# DC_SUPPLY.net
KiCad netlist of a schematic drawn in Altium Designer
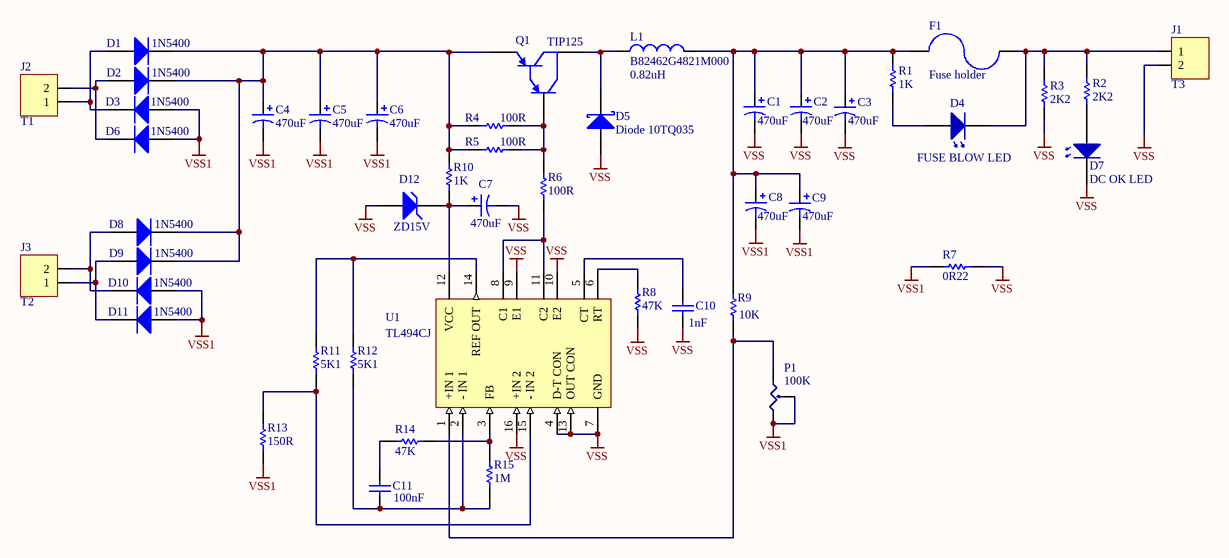
[diagram p0: DC SUPPLY.SchDoc]

(export (version "E")
  (design (tool "Eeschema 10.0.6"))
  (components
    (comp (ref "C1")
      (value "470uF")
      (footprint "CAPPR5-10X16")
      (description "Aluminum Electrolytic Capacitor, Radial Style with Long Leads: 470uF, 35V")
      (fields (field (name "PUBLISHER") "Altium Limited"))
      (libsource (lib "Vishay Roederstein Electrolytic Radial-Lead Capacitor") (part "EKA00DD347F00"))
    )
    (comp (ref "C2")
      (value "470uF")
      (footprint "CAPPR5-10X16")
      (description "Aluminum Electrolytic Capacitor, Radial Style with Long Leads: 470uF, 35V")
      (fields (field (name "PUBLISHER") "Altium Limited"))
      (libsource (lib "Vishay Roederstein Electrolytic Radial-Lead Capacitor") (part "EKA00DD347F00"))
    )
    (comp (ref "C3")
      (value "470uF")
      (footprint "CAPPR5-10X16")
      (description "Aluminum Electrolytic Capacitor, Radial Style with Long Leads: 470uF, 35V")
      (fields (field (name "PUBLISHER") "Altium Limited"))
      (libsource (lib "Vishay Roederstein Electrolytic Radial-Lead Capacitor") (part "EKA00DD347F00"))
    )
    (comp (ref "C4")
      (value "470uF")
      (footprint "CAPPR5-10X16")
      (description "Aluminum Electrolytic Capacitor, Radial Style with Long Leads: 470uF, 35V")
      (fields (field (name "PUBLISHER") "Altium Limited"))
      (libsource (lib "Vishay Roederstein Electrolytic Radial-Lead Capacitor") (part "EKA00DD347F00"))
    )
    (comp (ref "C5")
      (value "470uF")
      (footprint "CAPPR5-10X16")
      (description "Aluminum Electrolytic Capacitor, Radial Style with Long Leads: 470uF, 35V")
      (fields (field (name "PUBLISHER") "Altium Limited"))
      (libsource (lib "Vishay Roederstein Electrolytic Radial-Lead Capacitor") (part "EKA00DD347F00"))
    )
    (comp (ref "C6")
      (value "470uF")
      (footprint "CAPPR5-10X16")
      (description "Aluminum Electrolytic Capacitor, Radial Style with Long Leads: 470uF, 35V")
      (fields (field (name "PUBLISHER") "Altium Limited"))
      (libsource (lib "Vishay Roederstein Electrolytic Radial-Lead Capacitor") (part "EKA00DD347F00"))
    )
    (comp (ref "C7")
      (value "470uF")
      (footprint "CAPPR5-10X16")
      (description "Aluminum Electrolytic Capacitor, Radial Style with Long Leads: 470uF, 35V")
      (fields (field (name "PUBLISHER") "Altium Limited"))
      (libsource (lib "Vishay Roederstein Electrolytic Radial-Lead Capacitor") (part "EKA00DD347F00"))
    )
    (comp (ref "C8")
      (value "470uF")
      (footprint "CAPPR5-10X16")
      (description "Aluminum Electrolytic Capacitor, Radial Style with Long Leads: 470uF, 35V")
      (fields (field (name "PUBLISHER") "Altium Limited"))
      (libsource (lib "Vishay Roederstein Electrolytic Radial-Lead Capacitor") (part "EKA00DD347F00"))
    )
    (comp (ref "C9")
      (value "470uF")
      (footprint "CAPPR5-10X16")
      (description "Aluminum Electrolytic Capacitor, Radial Style with Long Leads: 470uF, 35V")
      (fields (field (name "PUBLISHER") "Altium Limited"))
      (libsource (lib "Vishay Roederstein Electrolytic Radial-Lead Capacitor") (part "EKA00DD347F00"))
    )
    (comp (ref "C10")
      (value "1nF")
      (footprint "0805")
      (description "Ceramic Chip Capacitor - Standard")
      (fields (field (name "PUBLISHER") "Altium Limited"))
      (libsource (lib "KEMET Chip Capacitor") (part "C0805"))
    )
    (comp (ref "C11")
      (value "100nF")
      (footprint "0805")
      (description "Ceramic Chip Capacitor - Standard")
      (fields (field (name "PUBLISHER") "Altium Limited"))
      (libsource (lib "KEMET Chip Capacitor") (part "C0805"))
    )
    (comp (ref "D1")
      (value "1N5400")
      (footprint "DO-201AD")
      (description "3.0 Ampere General Purpose Rectifier")
      (fields (field (name "PUBLISHER") "Altium Limited"))
      (libsource (lib "FSC Discrete Rectifier") (part "1N5400"))
    )
    (comp (ref "D2")
      (value "1N5400")
      (footprint "DO-201AD")
      (description "3.0 Ampere General Purpose Rectifier")
      (fields (field (name "PUBLISHER") "Altium Limited"))
      (libsource (lib "FSC Discrete Rectifier") (part "1N5400"))
    )
    (comp (ref "D3")
      (value "1N5400")
      (footprint "DO-201AD")
      (description "3.0 Ampere General Purpose Rectifier")
      (fields (field (name "PUBLISHER") "Altium Limited"))
      (libsource (lib "FSC Discrete Rectifier") (part "1N5400"))
    )
    (comp (ref "D4")
      (value "FUSE BLOW LED")
      (footprint "LED 3 mm")
      (description "3mm LED")
      (libsource (lib "DC SUPPLY") (part "3mm LED"))
    )
    (comp (ref "D5")
      (value "Diode 10TQ035")
      (footprint "TO-220AC")
      (description "Schottky Rectifier")
      (fields (field (name "PUBLISHER") "Altium Limited"))
      (libsource (lib "Miscellaneous Devices") (part "Diode 10TQ035"))
    )
    (comp (ref "D6")
      (value "1N5400")
      (footprint "DO-201AD")
      (description "3.0 Ampere General Purpose Rectifier")
      (fields (field (name "PUBLISHER") "Altium Limited"))
      (libsource (lib "FSC Discrete Rectifier") (part "1N5400"))
    )
    (comp (ref "D7")
      (value "DC OK LED")
      (footprint "LED 3 mm")
      (description "3mm LED")
      (libsource (lib "DC SUPPLY") (part "3mm LED"))
    )
    (comp (ref "D8")
      (value "1N5400")
      (footprint "DO-201AD")
      (description "3.0 Ampere General Purpose Rectifier")
      (fields (field (name "PUBLISHER") "Altium Limited"))
      (libsource (lib "FSC Discrete Rectifier") (part "1N5400"))
    )
    (comp (ref "D9")
      (value "1N5400")
      (footprint "DO-201AD")
      (description "3.0 Ampere General Purpose Rectifier")
      (fields (field (name "PUBLISHER") "Altium Limited"))
      (libsource (lib "FSC Discrete Rectifier") (part "1N5400"))
    )
    (comp (ref "D10")
      (value "1N5400")
      (footprint "DO-201AD")
      (description "3.0 Ampere General Purpose Rectifier")
      (fields (field (name "PUBLISHER") "Altium Limited"))
      (libsource (lib "FSC Discrete Rectifier") (part "1N5400"))
    )
    (comp (ref "D11")
      (value "1N5400")
      (footprint "DO-201AD")
      (description "3.0 Ampere General Purpose Rectifier")
      (fields (field (name "PUBLISHER") "Altium Limited"))
      (libsource (lib "FSC Discrete Rectifier") (part "1N5400"))
    )
    (comp (ref "D12")
      (value "ZD15V")
      (footprint "299-02")
      (description "500 mW Hermetically Sealed Glass Silicon Zener Diode")
      (fields (field (name "PUBLISHER") "Altium Limited"))
      (libsource (lib "Motorola Discrete Diode") (part "1N746A"))
    )
    (comp (ref "F1")
      (value "Fuse holder")
      (footprint "FUSE HOLDER")
      (description "glas fuse holder")
      (libsource (lib "DC SUPPLY") (part "Fuse holder"))
    )
    (comp (ref "J1")
      (value "T3")
      (footprint "TERMINAL_BLOCK_2")
      (description "2 pins terminal block")
      (libsource (lib "") (part "Terminal block 2_1"))
    )
    (comp (ref "J2")
      (value "T1")
      (footprint "TERMINAL_BLOCK_2")
      (description "2 pins terminal block")
      (libsource (lib "DC SUPPLY") (part "Terminal block 2"))
    )
    (comp (ref "J3")
      (value "T2")
      (footprint "TERMINAL_BLOCK_2")
      (description "2 pins terminal block")
      (libsource (lib "DC SUPPLY") (part "Terminal block 2"))
    )
    (comp (ref "L1")
      (value "B82462G4821M000")
      (footprint "Vishay Roederstein Electrolytic Radial-Lead Capacitor:CAPPR5-10X16")
      (description "SMT Power Inductor; Size 6.3×6.3×3.0mm, ±20% Tolerance, 0.82uH, 3.45A")
      (fields (field (name "ALTIUM_VALUE") "0.82uH") (field (name "PUBLISHER") "Altium Limited"))
      (libsource (lib "EPCOS Inductor") (part "B82462G4821M000"))
    )
    (comp (ref "P1")
      (value "100K")
      (footprint "POT")
      (description "PIHER poti vertical pcb mounting")
      (libsource (lib "DC SUPPLY") (part "POT"))
    )
    (comp (ref "Q1")
      (value "TIP125")
      (footprint "221A-02")
      (description "Darlington Silicon Power PNP Transistor, 8 Amp, 60 Volts and 65 Watts")
      (fields (field (name "PUBLISHER") "Altium Limited"))
      (libsource (lib "Motorola Discrete BJT") (part "TIP125"))
    )
    (comp (ref "R1")
      (value "1K")
      (footprint "ERA-0805")
      (fields (field (name "PUBLISHER") "Altium Limited"))
      (libsource (lib "Panasonic Resistor") (part "ERA6Y"))
    )
    (comp (ref "R2")
      (value "2K2")
      (footprint "ERA-0805")
      (fields (field (name "PUBLISHER") "Altium Limited"))
      (libsource (lib "Panasonic Resistor") (part "ERA6Y"))
    )
    (comp (ref "R3")
      (value "2K2")
      (footprint "ERA-0805")
      (fields (field (name "PUBLISHER") "Altium Limited"))
      (libsource (lib "Panasonic Resistor") (part "ERA6Y"))
    )
    (comp (ref "R4")
      (value "100R")
      (footprint "RD3.2x1.7")
      (fields (field (name "PUBLISHER") "Altium Limited"))
      (libsource (lib "Panasonic Resistor") (part "ERD6FC"))
    )
    (comp (ref "R5")
      (value "100R")
      (footprint "RD3.2x1.7")
      (fields (field (name "PUBLISHER") "Altium Limited"))
      (libsource (lib "Panasonic Resistor") (part "ERD6FC"))
    )
    (comp (ref "R6")
      (value "100R")
      (footprint "RD3.2x1.7")
      (fields (field (name "PUBLISHER") "Altium Limited"))
      (libsource (lib "Panasonic Resistor") (part "ERD6FC"))
    )
    (comp (ref "R7")
      (value "0R22")
      (footprint "R9x2.8")
      (description "Metal Oxide Film Resistor, 0.1 Ohm to 100k Ohm Range, 2% and 5% Tolerance, 1 W")
      (fields (field (name "PUBLISHER") "Altium Limited"))
      (libsource (lib "Panasonic Resistor") (part "ERG1"))
    )
    (comp (ref "R8")
      (value "47K")
      (footprint "ERA-0805")
      (fields (field (name "PUBLISHER") "Altium Limited"))
      (libsource (lib "Panasonic Resistor") (part "ERA6Y"))
    )
    (comp (ref "R9")
      (value "10K")
      (footprint "ERA-0805")
      (fields (field (name "PUBLISHER") "Altium Limited"))
      (libsource (lib "Panasonic Resistor") (part "ERA6Y"))
    )
    (comp (ref "R10")
      (value "1K")
      (footprint "RD6.35x2.3")
      (description "Carbon Film Resistor, 1 Ohm to 3.3M Ohm Range, 5% Tolerance, 0.5 W")
      (fields (field (name "PUBLISHER") "Altium Limited"))
      (libsource (lib "Panasonic Resistor") (part "ERDS1T"))
    )
    (comp (ref "R11")
      (value "5K1")
      (footprint "ERA-0805")
      (fields (field (name "PUBLISHER") "Altium Limited"))
      (libsource (lib "Panasonic Resistor") (part "ERA6Y"))
    )
    (comp (ref "R12")
      (value "5K1")
      (footprint "ERA-0805")
      (fields (field (name "PUBLISHER") "Altium Limited"))
      (libsource (lib "Panasonic Resistor") (part "ERA6Y"))
    )
    (comp (ref "R13")
      (value "150R")
      (footprint "ERA-0805")
      (fields (field (name "PUBLISHER") "Altium Limited"))
      (libsource (lib "Panasonic Resistor") (part "ERA6Y"))
    )
    (comp (ref "R14")
      (value "47K")
      (footprint "ERA-0805")
      (fields (field (name "PUBLISHER") "Altium Limited"))
      (libsource (lib "Panasonic Resistor") (part "ERA6Y"))
    )
    (comp (ref "R15")
      (value "1M")
      (footprint "ERA-0805")
      (fields (field (name "PUBLISHER") "Altium Limited"))
      (libsource (lib "Panasonic Resistor") (part "ERA6Y"))
    )
    (comp (ref "U1")
      (value "TL494CJ")
      (footprint "J016")
      (description "Pulse-Width-Modulation Control Circuit")
      (fields (field (name "PUBLISHER") "Altium Limited"))
      (libsource (lib "TI Power Mgt Power Controller") (part "TL494CJ"))
    )
  )
  (nets
    (net (code "1") (name "Net-(C1-Pad1)") (class "Default")
      (node (ref "C1") (pin "1") (pinfunction "1_1") (pintype "passive"))
      (node (ref "C2") (pin "1") (pinfunction "1_1") (pintype "passive"))
      (node (ref "C3") (pin "1") (pinfunction "1_1") (pintype "passive"))
      (node (ref "C8") (pin "1") (pinfunction "1_1") (pintype "passive"))
      (node (ref "C9") (pin "1") (pinfunction "1_1") (pintype "passive"))
      (node (ref "F1") (pin "1") (pinfunction "1_1") (pintype "passive"))
      (node (ref "L1") (pin "2") (pinfunction "2_2") (pintype "passive"))
      (node (ref "R1") (pin "2") (pinfunction "2_2") (pintype "passive"))
      (node (ref "R9") (pin "2") (pinfunction "2_2") (pintype "passive"))
    )
    (net (code "2") (name "Net-(C11-Pad1)") (class "Default")
      (node (ref "C11") (pin "1") (pinfunction "1_1") (pintype "passive"))
      (node (ref "R14") (pin "1") (pinfunction "1_1") (pintype "passive"))
    )
    (net (code "3") (name "Net-(D1-A)") (class "Default")
      (node (ref "D1") (pin "1") (pinfunction "A_1") (pintype "passive"))
      (node (ref "D3") (pin "2") (pinfunction "K_2") (pintype "passive"))
      (node (ref "J2") (pin "1") (pinfunction "1_1") (pintype "passive"))
    )
    (net (code "4") (name "Net-(D1-K)") (class "Default")
      (node (ref "C4") (pin "1") (pinfunction "1_1") (pintype "passive"))
      (node (ref "C5") (pin "1") (pinfunction "1_1") (pintype "passive"))
      (node (ref "C6") (pin "1") (pinfunction "1_1") (pintype "passive"))
      (node (ref "D1") (pin "2") (pinfunction "K_2") (pintype "passive"))
      (node (ref "D2") (pin "2") (pinfunction "K_2") (pintype "passive"))
      (node (ref "D8") (pin "2") (pinfunction "K_2") (pintype "passive"))
      (node (ref "D9") (pin "2") (pinfunction "K_2") (pintype "passive"))
      (node (ref "Q1") (pin "3") (pinfunction "E_3") (pintype "passive"))
      (node (ref "R10") (pin "2") (pinfunction "2_2") (pintype "passive"))
      (node (ref "R4") (pin "1") (pinfunction "1_1") (pintype "passive"))
      (node (ref "R5") (pin "1") (pinfunction "1_1") (pintype "passive"))
    )
    (net (code "5") (name "Net-(D2-A)") (class "Default")
      (node (ref "D2") (pin "1") (pinfunction "A_1") (pintype "passive"))
      (node (ref "D6") (pin "2") (pinfunction "K_2") (pintype "passive"))
      (node (ref "J2") (pin "2") (pinfunction "2_2") (pintype "passive"))
    )
    (net (code "6") (name "Net-(D4-Pad1)") (class "Default")
      (node (ref "D4") (pin "1") (pinfunction "1_1") (pintype "passive"))
      (node (ref "F1") (pin "2") (pinfunction "2_2") (pintype "passive"))
      (node (ref "J1") (pin "1") (pinfunction "1_1") (pintype "passive"))
      (node (ref "R2") (pin "2") (pinfunction "2_2") (pintype "passive"))
      (node (ref "R3") (pin "2") (pinfunction "2_2") (pintype "passive"))
    )
    (net (code "7") (name "Net-(D4-Pad2)") (class "Default")
      (node (ref "D4") (pin "2") (pinfunction "2_2") (pintype "passive"))
      (node (ref "R1") (pin "1") (pinfunction "1_1") (pintype "passive"))
    )
    (net (code "8") (name "Net-(D5-K)") (class "Default")
      (node (ref "D5") (pin "1") (pinfunction "K_1") (pintype "passive"))
      (node (ref "L1") (pin "1") (pinfunction "1_1") (pintype "passive"))
      (node (ref "Q1") (pin "2") (pinfunction "C_2") (pintype "passive"))
    )
    (net (code "9") (name "Net-(D7-Pad2)") (class "Default")
      (node (ref "D7") (pin "2") (pinfunction "2_2") (pintype "passive"))
      (node (ref "R2") (pin "1") (pinfunction "1_1") (pintype "passive"))
    )
    (net (code "10") (name "Net-(D10-K)") (class "Default")
      (node (ref "D10") (pin "2") (pinfunction "K_2") (pintype "passive"))
      (node (ref "D8") (pin "1") (pinfunction "A_1") (pintype "passive"))
      (node (ref "J3") (pin "2") (pinfunction "2_2") (pintype "passive"))
    )
    (net (code "11") (name "Net-(D11-K)") (class "Default")
      (node (ref "D11") (pin "2") (pinfunction "K_2") (pintype "passive"))
      (node (ref "D9") (pin "1") (pinfunction "A_1") (pintype "passive"))
      (node (ref "J3") (pin "1") (pinfunction "1_1") (pintype "passive"))
    )
    (net (code "12") (name "Net-(D12-K)") (class "Default")
      (node (ref "C7") (pin "1") (pinfunction "1_1") (pintype "passive"))
      (node (ref "D12") (pin "2") (pinfunction "K_2") (pintype "passive"))
      (node (ref "R10") (pin "1") (pinfunction "1_1") (pintype "passive"))
      (node (ref "U1") (pin "12") (pinfunction "VCC_12") (pintype "power_in"))
    )
    (net (code "13") (name "Net-(Q1-B)") (class "Default")
      (node (ref "Q1") (pin "1") (pinfunction "B_1") (pintype "passive"))
      (node (ref "R4") (pin "2") (pinfunction "2_2") (pintype "passive"))
      (node (ref "R5") (pin "2") (pinfunction "2_2") (pintype "passive"))
      (node (ref "R6") (pin "2") (pinfunction "2_2") (pintype "passive"))
    )
    (net (code "14") (name "Net-(U1-+IN_1)") (class "Default")
      (node (ref "P1") (pin "1") (pinfunction "1_1") (pintype "passive"))
      (node (ref "R9") (pin "1") (pinfunction "1_1") (pintype "passive"))
      (node (ref "U1") (pin "1") (pinfunction "+IN_1_1") (pintype "input"))
    )
    (net (code "15") (name "Net-(U1--_IN_1)") (class "Default")
      (node (ref "C11") (pin "2") (pinfunction "2_2") (pintype "passive"))
      (node (ref "R12") (pin "1") (pinfunction "1_1") (pintype "passive"))
      (node (ref "R15") (pin "1") (pinfunction "1_1") (pintype "passive"))
      (node (ref "U1") (pin "2") (pinfunction "-_IN_1_2") (pintype "input"))
    )
    (net (code "16") (name "Net-(U1--_IN_2)") (class "Default")
      (node (ref "R11") (pin "1") (pinfunction "1_1") (pintype "passive"))
      (node (ref "R13") (pin "2") (pinfunction "2_2") (pintype "passive"))
      (node (ref "U1") (pin "15") (pinfunction "-_IN_2_15") (pintype "input"))
    )
    (net (code "17") (name "Net-(U1-C1)") (class "Default")
      (node (ref "R6") (pin "1") (pinfunction "1_1") (pintype "passive"))
      (node (ref "U1") (pin "11") (pinfunction "C2_11") (pintype "passive"))
      (node (ref "U1") (pin "8") (pinfunction "C1_8") (pintype "passive"))
    )
    (net (code "18") (name "Net-(U1-CT)") (class "Default")
      (node (ref "C10") (pin "2") (pinfunction "2_2") (pintype "passive"))
      (node (ref "U1") (pin "5") (pinfunction "CT_5") (pintype "passive"))
    )
    (net (code "19") (name "Net-(U1-FB)") (class "Default")
      (node (ref "R14") (pin "2") (pinfunction "2_2") (pintype "passive"))
      (node (ref "R15") (pin "2") (pinfunction "2_2") (pintype "passive"))
      (node (ref "U1") (pin "3") (pinfunction "FB_3") (pintype "input"))
    )
    (net (code "20") (name "Net-(U1-REF_OUT)") (class "Default")
      (node (ref "R11") (pin "2") (pinfunction "2_2") (pintype "passive"))
      (node (ref "R12") (pin "2") (pinfunction "2_2") (pintype "passive"))
      (node (ref "U1") (pin "14") (pinfunction "REF_OUT_14") (pintype "output"))
    )
    (net (code "21") (name "Net-(U1-RT)") (class "Default")
      (node (ref "R8") (pin "2") (pinfunction "2_2") (pintype "passive"))
      (node (ref "U1") (pin "6") (pinfunction "RT_6") (pintype "passive"))
    )
    (net (code "22") (name "VSS") (class "Default")
      (node (ref "C1") (pin "2") (pinfunction "2_2") (pintype "passive"))
      (node (ref "C10") (pin "1") (pinfunction "1_1") (pintype "passive"))
      (node (ref "C2") (pin "2") (pinfunction "2_2") (pintype "passive"))
      (node (ref "C3") (pin "2") (pinfunction "2_2") (pintype "passive"))
      (node (ref "C7") (pin "2") (pinfunction "2_2") (pintype "passive"))
      (node (ref "D12") (pin "1") (pinfunction "A_1") (pintype "passive"))
      (node (ref "D5") (pin "3") (pinfunction "A_3") (pintype "passive"))
      (node (ref "D7") (pin "1") (pinfunction "1_1") (pintype "passive"))
      (node (ref "J1") (pin "2") (pinfunction "2_2") (pintype "passive"))
      (node (ref "R3") (pin "1") (pinfunction "1_1") (pintype "passive"))
      (node (ref "R7") (pin "2") (pinfunction "2_2") (pintype "passive"))
      (node (ref "R8") (pin "1") (pinfunction "1_1") (pintype "passive"))
      (node (ref "U1") (pin "10") (pinfunction "E2_10") (pintype "passive"))
      (node (ref "U1") (pin "13") (pinfunction "OUT_CON_13") (pintype "input"))
      (node (ref "U1") (pin "16") (pinfunction "+IN_2_16") (pintype "input"))
      (node (ref "U1") (pin "4") (pinfunction "D-T_CON_4") (pintype "input"))
      (node (ref "U1") (pin "7") (pinfunction "GND_7") (pintype "power_in"))
      (node (ref "U1") (pin "9") (pinfunction "E1_9") (pintype "passive"))
    )
    (net (code "23") (name "VSS1") (class "Default")
      (node (ref "C4") (pin "2") (pinfunction "2_2") (pintype "passive"))
      (node (ref "C5") (pin "2") (pinfunction "2_2") (pintype "passive"))
      (node (ref "C6") (pin "2") (pinfunction "2_2") (pintype "passive"))
      (node (ref "C8") (pin "2") (pinfunction "2_2") (pintype "passive"))
      (node (ref "C9") (pin "2") (pinfunction "2_2") (pintype "passive"))
      (node (ref "D10") (pin "1") (pinfunction "A_1") (pintype "passive"))
      (node (ref "D11") (pin "1") (pinfunction "A_1") (pintype "passive"))
      (node (ref "D3") (pin "1") (pinfunction "A_1") (pintype "passive"))
      (node (ref "D6") (pin "1") (pinfunction "A_1") (pintype "passive"))
      (node (ref "P1") (pin "2") (pinfunction "2_2") (pintype "passive"))
      (node (ref "P1") (pin "3") (pinfunction "3_3") (pintype "passive"))
      (node (ref "R13") (pin "1") (pinfunction "1_1") (pintype "passive"))
      (node (ref "R7") (pin "1") (pinfunction "1_1") (pintype "passive"))
    )
  )
)
